# IMU.net
KiCad netlist of a schematic drawn in Altium Designer
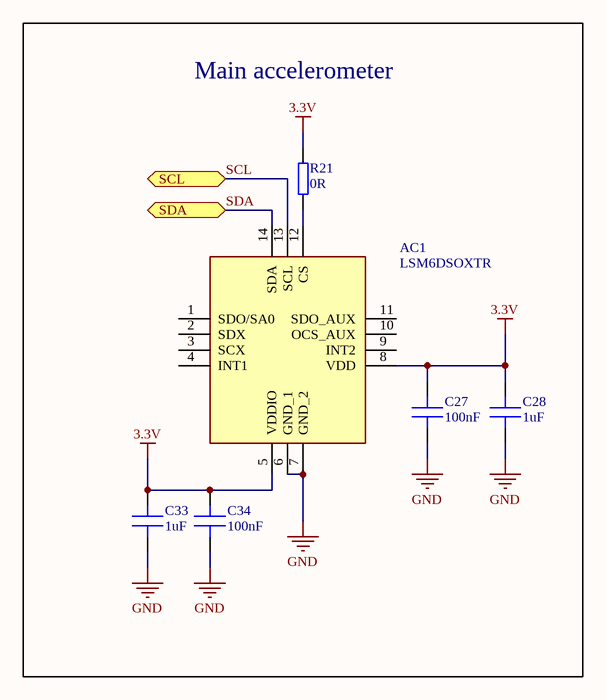
[diagram p0: IMU.SchDoc]

(export (version "E")
  (design (tool "Eeschema 10.0.6"))
  (components
    (comp (ref "AC1")
      (value "LSM6DSOXTR")
      (footprint "SamacSys:LGA-14_1")
      (description "Accelerometer")
      (fields (field (name "MOUSER PART NUMBER") "511-LSM6DSOXTR"))
      (libsource (lib "caravan_sch_lib") (part "LSM6DSOXTR"))
    )
    (comp (ref "C27")
      (value "100nF")
      (footprint "C 0402")
      (description "MLCC Capacitor")
      (libsource (lib "Components") (part "Capacitor"))
    )
    (comp (ref "C28")
      (value "1uF")
      (footprint "C 0402")
      (description "MLCC Capacitor")
      (libsource (lib "Components") (part "Capacitor"))
    )
    (comp (ref "C33")
      (value "1uF")
      (footprint "C 0402")
      (description "MLCC Capacitor")
      (libsource (lib "Components") (part "Capacitor"))
    )
    (comp (ref "C34")
      (value "100nF")
      (footprint "C 0402")
      (description "MLCC Capacitor")
      (libsource (lib "Components") (part "Capacitor"))
    )
    (comp (ref "R21")
      (value "0R")
      (footprint "R 0402")
      (description "General pourpouse resistor")
      (libsource (lib "Components") (part "Resistor"))
    )
  )
  (nets
    (net (code "1") (name "/SCL") (class "Default")
      (node (ref "AC1") (pin "13") (pinfunction "SCL_13") (pintype "passive"))
    )
    (net (code "2") (name "/SDA") (class "Default")
      (node (ref "AC1") (pin "14") (pinfunction "SDA_14") (pintype "passive"))
    )
    (net (code "3") (name "3.3V") (class "Default")
      (node (ref "AC1") (pin "5") (pinfunction "VDDIO_5") (pintype "passive"))
      (node (ref "AC1") (pin "8") (pinfunction "VDD_8") (pintype "passive"))
      (node (ref "C27") (pin "1") (pinfunction "1_1") (pintype "passive"))
      (node (ref "C28") (pin "1") (pinfunction "1_1") (pintype "passive"))
      (node (ref "C33") (pin "1") (pinfunction "1_1") (pintype "passive"))
      (node (ref "C34") (pin "1") (pinfunction "1_1") (pintype "passive"))
      (node (ref "R21") (pin "2") (pinfunction "2_2") (pintype "passive"))
    )
    (net (code "4") (name "GND") (class "Default")
      (node (ref "AC1") (pin "6") (pinfunction "GND_1_6") (pintype "passive"))
      (node (ref "AC1") (pin "7") (pinfunction "GND_2_7") (pintype "passive"))
      (node (ref "C27") (pin "2") (pinfunction "2_2") (pintype "passive"))
      (node (ref "C28") (pin "2") (pinfunction "2_2") (pintype "passive"))
      (node (ref "C33") (pin "2") (pinfunction "2_2") (pintype "passive"))
      (node (ref "C34") (pin "2") (pinfunction "2_2") (pintype "passive"))
    )
    (net (code "5") (name "Net-(AC1-CS)") (class "Default")
      (node (ref "AC1") (pin "12") (pinfunction "CS_12") (pintype "passive"))
      (node (ref "R21") (pin "1") (pinfunction "1_1") (pintype "passive"))
    )
    (net (code "6") (name "unconnected-(AC1-INT1-Pad4)") (class "Default")
      (node (ref "AC1") (pin "4") (pinfunction "INT1_4") (pintype "passive"))
    )
    (net (code "7") (name "unconnected-(AC1-INT2-Pad9)") (class "Default")
      (node (ref "AC1") (pin "9") (pinfunction "INT2_9") (pintype "passive"))
    )
    (net (code "8") (name "unconnected-(AC1-OCS_AUX-Pad10)") (class "Default")
      (node (ref "AC1") (pin "10") (pinfunction "OCS_AUX_10") (pintype "passive"))
    )
    (net (code "9") (name "unconnected-(AC1-SCX-Pad3)") (class "Default")
      (node (ref "AC1") (pin "3") (pinfunction "SCX_3") (pintype "passive"))
    )
    (net (code "10") (name "unconnected-(AC1-SDO_AUX-Pad11)") (class "Default")
      (node (ref "AC1") (pin "11") (pinfunction "SDO_AUX_11") (pintype "passive"))
    )
    (net (code "11") (name "unconnected-(AC1-SDO{slash}SA0-Pad1)") (class "Default")
      (node (ref "AC1") (pin "1") (pinfunction "SDO/SA0_1") (pintype "passive"))
    )
    (net (code "12") (name "unconnected-(AC1-SDX-Pad2)") (class "Default")
      (node (ref "AC1") (pin "2") (pinfunction "SDX_2") (pintype "passive"))
    )
  )
)
